# Main_CPU.net
KiCad netlist of a schematic drawn in Altium Designer
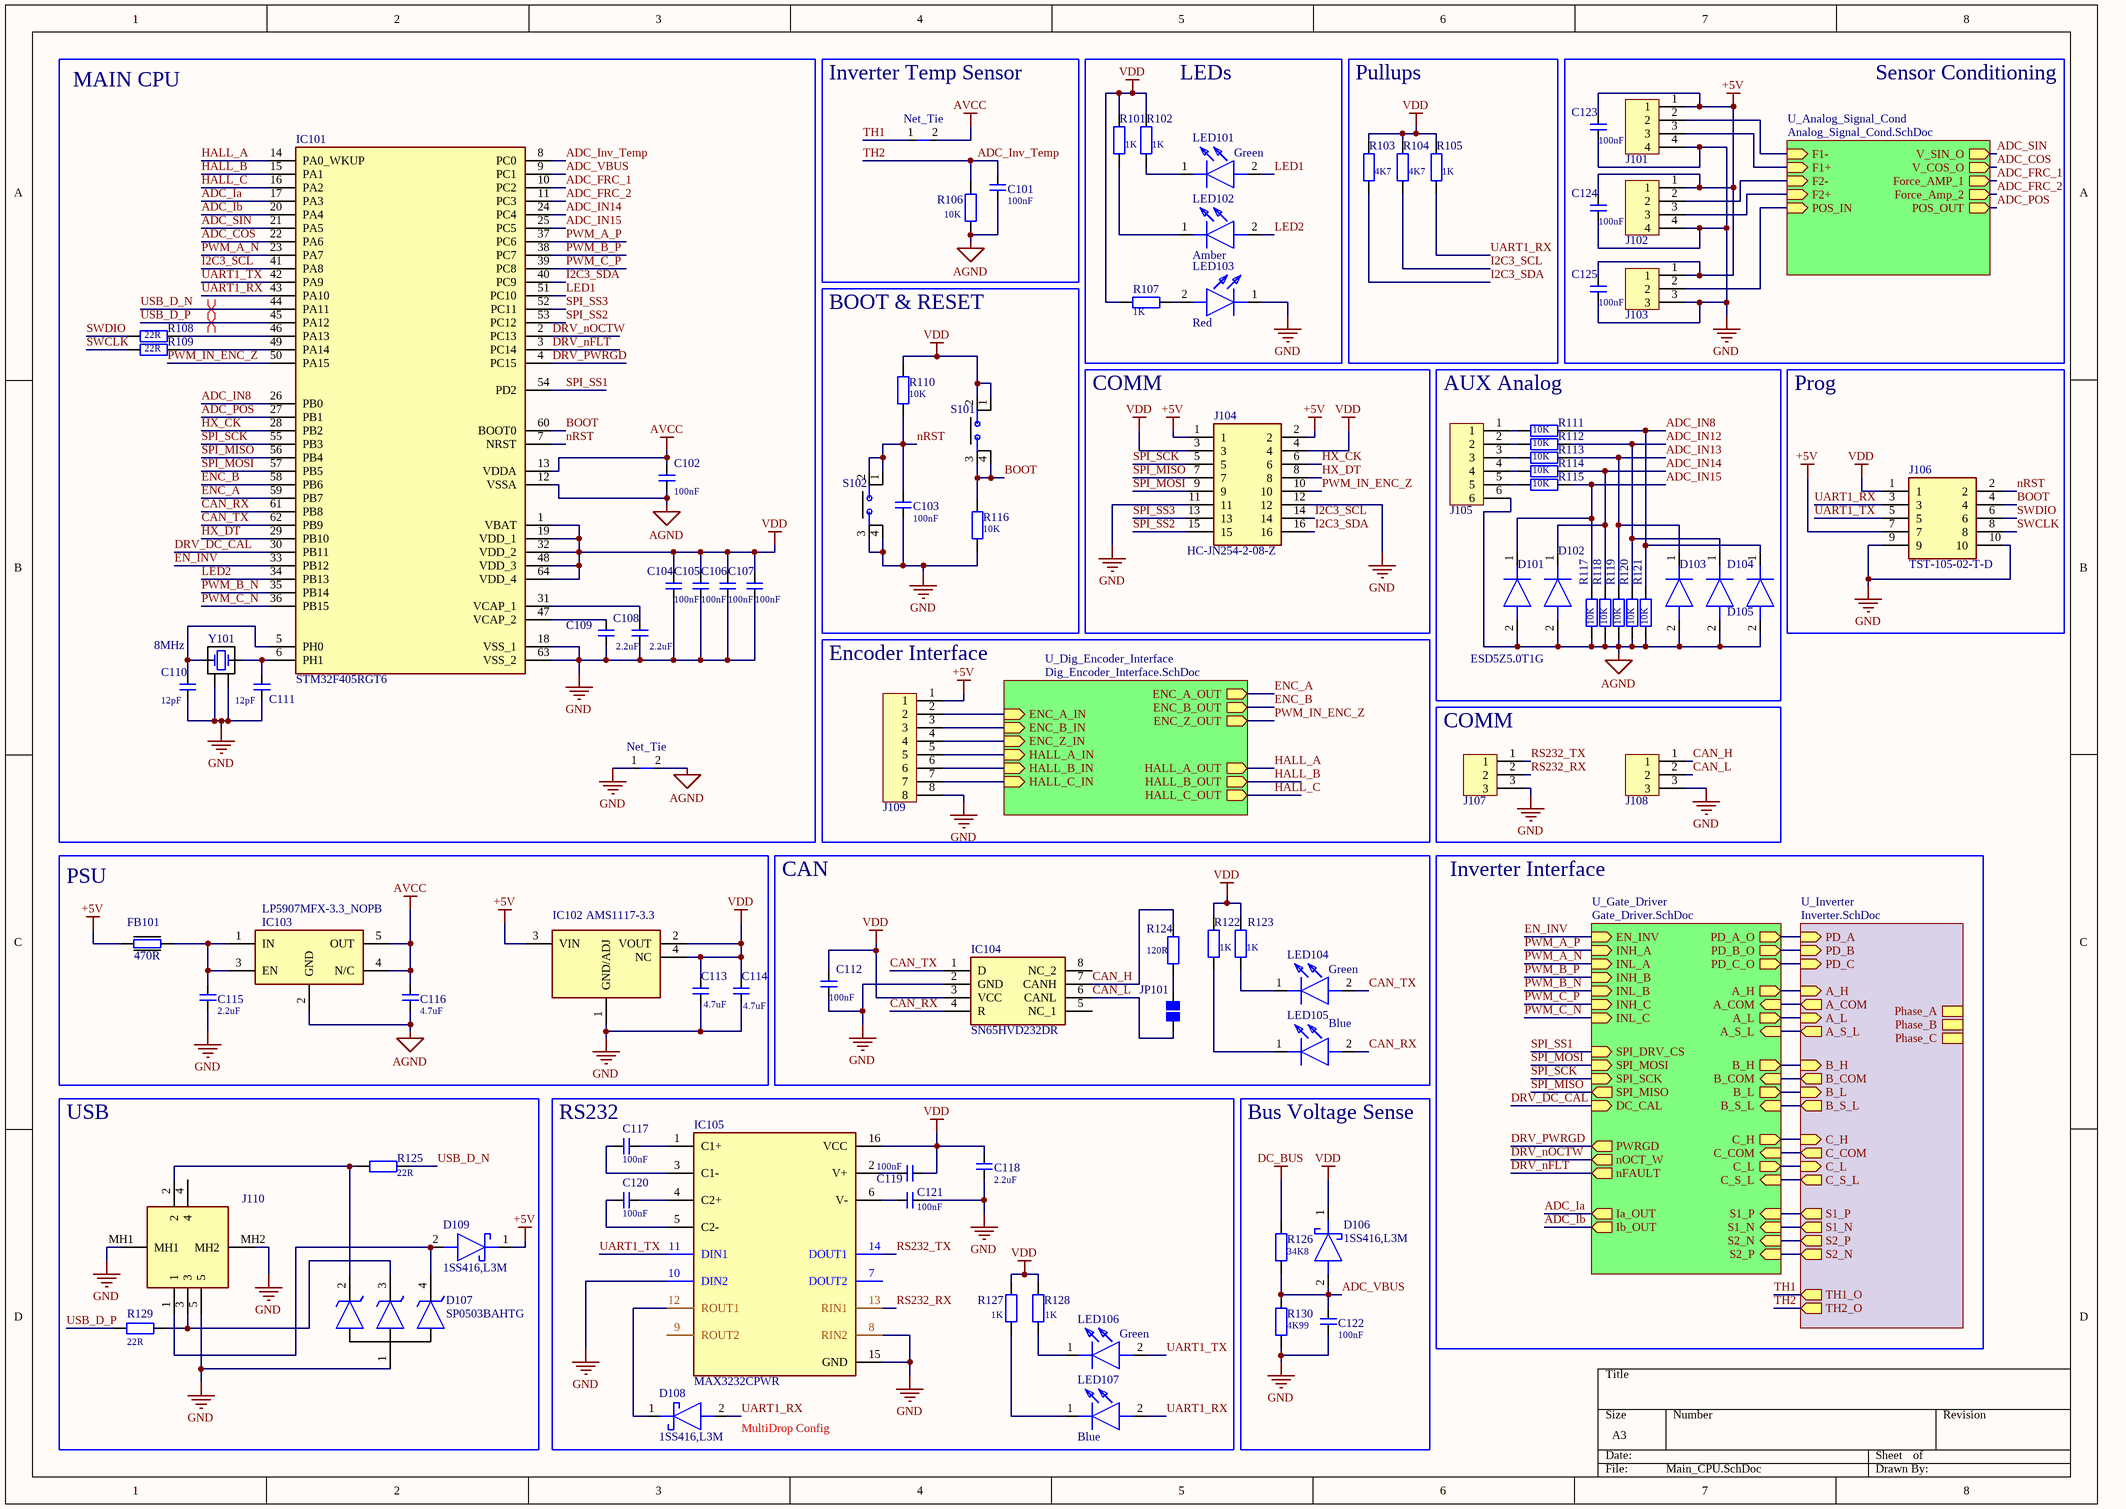
[diagram p0: Main_CPU.SchDoc]

(export (version "E")
  (design (tool "Eeschema 10.0.6"))
  (components
    (comp (ref "C101")
      (value "100nF")
      (footprint "CAPC1005X06N")
      (description "Capacitor")
      (fields (field (name "MPN") "GCM155R71H104KE02D") (field (name "Comment") "Cap"))
      (libsource (lib "SamacSys") (part "Cap"))
    )
    (comp (ref "C102")
      (value "100nF")
      (footprint "CAPC1005X06N")
      (description "Capacitor")
      (fields (field (name "MPN") "GCM155R71H104KE02D") (field (name "Comment") "Cap"))
      (libsource (lib "SamacSys") (part "Cap"))
    )
    (comp (ref "C103")
      (value "100nF")
      (footprint "CAPC1005X06N")
      (description "Capacitor")
      (fields (field (name "MPN") "GCM155R71H104KE02D") (field (name "Comment") "Cap"))
      (libsource (lib "SamacSys") (part "Cap"))
    )
    (comp (ref "C104")
      (value "100nF")
      (footprint "CAPC1005X06N")
      (description "Capacitor")
      (fields (field (name "MPN") "GCM155R71H104KE02D") (field (name "Comment") "Cap"))
      (libsource (lib "SamacSys") (part "Cap"))
    )
    (comp (ref "C105")
      (value "100nF")
      (footprint "CAPC1005X06N")
      (description "Capacitor")
      (fields (field (name "MPN") "GCM155R71H104KE02D") (field (name "Comment") "Cap"))
      (libsource (lib "SamacSys") (part "Cap"))
    )
    (comp (ref "C106")
      (value "100nF")
      (footprint "CAPC1005X06N")
      (description "Capacitor")
      (fields (field (name "MPN") "GCM155R71H104KE02D") (field (name "Comment") "Cap"))
      (libsource (lib "SamacSys") (part "Cap"))
    )
    (comp (ref "C107")
      (value "100nF")
      (footprint "CAPC1005X06N")
      (description "Capacitor")
      (fields (field (name "MPN") "GCM155R71H104KE02D") (field (name "Comment") "Cap"))
      (libsource (lib "SamacSys") (part "Cap"))
    )
    (comp (ref "C108")
      (value "2.2uF")
      (footprint "CAPC1005X06N")
      (description "Capacitor")
      (fields (field (name "MPN") "GRM155Z71A225KE44D") (field (name "Comment") "Cap"))
      (libsource (lib "SamacSys") (part "Cap"))
    )
    (comp (ref "C109")
      (value "2.2uF")
      (footprint "CAPC1005X06N")
      (description "Capacitor")
      (fields (field (name "MPN") "GRM155Z71A225KE44D") (field (name "Comment") "Cap"))
      (libsource (lib "SamacSys") (part "Cap"))
    )
    (comp (ref "C110")
      (value "12pF")
      (footprint "CAPC1005X06N")
      (description "Capacitor")
      (fields (field (name "MPN") "GRM1555C1H120JA01D") (field (name "Comment") "Cap"))
      (libsource (lib "SamacSys") (part "Cap"))
    )
    (comp (ref "C111")
      (value "12pF")
      (footprint "CAPC1005X06N")
      (description "Capacitor")
      (fields (field (name "MPN") "GRM1555C1H120JA01D") (field (name "Comment") "Cap"))
      (libsource (lib "SamacSys") (part "Cap"))
    )
    (comp (ref "C112")
      (value "100nF")
      (footprint "CAPC1005X06N")
      (description "Capacitor")
      (fields (field (name "MPN") "GCM155R71H104KE02D") (field (name "Comment") "Cap"))
      (libsource (lib "SamacSys") (part "Cap"))
    )
    (comp (ref "C113")
      (value "4.7uF")
      (footprint "CAPC3225X17N")
      (description "Capacitor")
      (fields (field (name "MPN") "CC1210KKX7R8BB475") (field (name "Comment") "Cap"))
      (libsource (lib "SamacSys") (part "Cap"))
    )
    (comp (ref "C114")
      (value "4.7uF")
      (footprint "CAPC3225X17N")
      (description "Capacitor")
      (fields (field (name "MPN") "CC1210KKX7R8BB475") (field (name "Comment") "Cap"))
      (libsource (lib "SamacSys") (part "Cap"))
    )
    (comp (ref "C115")
      (value "2.2uF")
      (footprint "CAPC1005X06N")
      (description "Capacitor")
      (fields (field (name "MPN") "GRM155Z71A225KE44D") (field (name "Comment") "Cap"))
      (libsource (lib "SamacSys") (part "Cap"))
    )
    (comp (ref "C116")
      (value "4.7uF")
      (footprint "CAPC3225X17N")
      (description "Capacitor")
      (fields (field (name "MPN") "CC1210KKX7R8BB475") (field (name "Comment") "Cap"))
      (libsource (lib "SamacSys") (part "Cap"))
    )
    (comp (ref "C117")
      (value "100nF")
      (footprint "CAPC1005X06N")
      (description "Capacitor")
      (fields (field (name "MPN") "GCM155R71H104KE02D") (field (name "Comment") "Cap"))
      (libsource (lib "SamacSys") (part "Cap"))
    )
    (comp (ref "C118")
      (value "2.2uF")
      (footprint "CAPC1005X06N")
      (description "Capacitor")
      (fields (field (name "MPN") "GRM155Z71A225KE44D") (field (name "Comment") "Cap"))
      (libsource (lib "SamacSys") (part "Cap"))
    )
    (comp (ref "C119")
      (value "100nF")
      (footprint "CAPC1005X06N")
      (description "Capacitor")
      (fields (field (name "MPN") "GCM155R71H104KE02D") (field (name "Comment") "Cap"))
      (libsource (lib "SamacSys") (part "Cap"))
    )
    (comp (ref "C120")
      (value "100nF")
      (footprint "CAPC1005X06N")
      (description "Capacitor")
      (fields (field (name "MPN") "GCM155R71H104KE02D") (field (name "Comment") "Cap"))
      (libsource (lib "SamacSys") (part "Cap"))
    )
    (comp (ref "C121")
      (value "100nF")
      (footprint "CAPC1005X06N")
      (description "Capacitor")
      (fields (field (name "MPN") "GCM155R71H104KE02D") (field (name "Comment") "Cap"))
      (libsource (lib "SamacSys") (part "Cap"))
    )
    (comp (ref "C122")
      (value "100nF")
      (footprint "CAPC1005X06N")
      (description "Capacitor")
      (fields (field (name "MPN") "GCM155R71H104KE02D") (field (name "Comment") "Cap"))
      (libsource (lib "SamacSys") (part "Cap"))
    )
    (comp (ref "C123")
      (value "100nF")
      (footprint "CAPC1005X06N")
      (description "Capacitor")
      (fields (field (name "MPN") "GCM155R71H104KE02D") (field (name "Comment") "Cap"))
      (libsource (lib "SamacSys") (part "Cap"))
    )
    (comp (ref "C124")
      (value "100nF")
      (footprint "CAPC1005X06N")
      (description "Capacitor")
      (fields (field (name "MPN") "GCM155R71H104KE02D") (field (name "Comment") "Cap"))
      (libsource (lib "SamacSys") (part "Cap"))
    )
    (comp (ref "C125")
      (value "100nF")
      (footprint "CAPC1005X06N")
      (description "Capacitor")
      (fields (field (name "MPN") "GCM155R71H104KE02D") (field (name "Comment") "Cap"))
      (libsource (lib "SamacSys") (part "Cap"))
    )
    (comp (ref "D101")
      (value "ESD5Z5.0T1G")
      (footprint "SamacSys:SODFL1608X70N")
      (description "Diode")
      (fields (field (name "MOUSER PART NUMBER") "863-ESD5Z5.0T1G"))
      (libsource (lib "SamacSys") (part "ESD5Z5.0T1G"))
    )
    (comp (ref "D102")
      (value "ESD5Z5.0T1G")
      (footprint "SamacSys:SODFL1608X70N")
      (description "Diode")
      (fields (field (name "MPN") "863-ESD5Z5.0T1G"))
      (libsource (lib "SamacSys") (part "ESD5Z5.0T1G"))
    )
    (comp (ref "D103")
      (value "ESD5Z5.0T1G")
      (footprint "SamacSys:SODFL1608X70N")
      (description "Diode")
      (fields (field (name "MPN") "863-ESD5Z5.0T1G"))
      (libsource (lib "SamacSys") (part "ESD5Z5.0T1G"))
    )
    (comp (ref "D104")
      (value "ESD5Z5.0T1G")
      (footprint "SamacSys:SODFL1608X70N")
      (description "Diode")
      (fields (field (name "MPN") "863-ESD5Z5.0T1G"))
      (libsource (lib "SamacSys") (part "ESD5Z5.0T1G"))
    )
    (comp (ref "D105")
      (value "ESD5Z5.0T1G")
      (footprint "SamacSys:SODFL1608X70N")
      (description "Diode")
      (fields (field (name "MOUSER PART NUMBER") "863-ESD5Z5.0T1G"))
      (libsource (lib "SamacSys") (part "ESD5Z5.0T1G"))
    )
    (comp (ref "D106")
      (value "1SS416,L3M")
      (footprint "SamacSys:SODFL1006X45N")
      (description "Schottky Diode")
      (fields (field (name "MPN") "1SS416,L3M(B") (field (name "MOUSER PART NUMBER") "757-1SS416L3M"))
      (libsource (lib "SamacSys") (part "1SS416,L3M"))
    )
    (comp (ref "D107")
      (value "SP0503BAHTG")
      (footprint "SP0503BAHTG")
      (description "TVS Diode (Uni-directional)")
      (fields (field (name "MOUSER PART NUMBER") "576-SP0503BAHTG"))
      (libsource (lib "SamacSys") (part "SP0503BAHTG"))
    )
    (comp (ref "D108")
      (value "1SS416,L3M")
      (footprint "SamacSys:SODFL1006X45N")
      (description "Schottky Diode")
      (fields (field (name "MPN") "1SS416,L3M(B") (field (name "MOUSER PART NUMBER") "757-1SS416L3M"))
      (libsource (lib "SamacSys") (part "1SS416,L3M"))
    )
    (comp (ref "D109")
      (value "1SS416,L3M")
      (footprint "SODFL1006X45N")
      (description "Schottky Diode")
      (fields (field (name "MPN") "1SS416,L3M(B") (field (name "MOUSER PART NUMBER") "757-1SS416L3M"))
      (libsource (lib "SamacSys") (part "1SS416,L3M"))
    )
    (comp (ref "FB101")
      (value "470R")
      (footprint "SamacSys:BLM18SP221SN1B")
      (description "Ferrite Bead")
      (fields (field (name "MPN") "BLM18KG471SN1D") (field (name "MOUSER PART NUMBER") "81-BLM18KG471SN1D"))
      (libsource (lib "SamacSys") (part "BLM18KG471SN1D"))
    )
    (comp (ref "IC101")
      (value "STM32F405RGT6")
      (footprint "SamacSys:QFP50P1200X1200X160-64N")
      (description "Integrated Circuit")
      (fields (field (name "MOUSER PART NUMBER") "511-STM32F405RGT6"))
      (libsource (lib "SamacSys") (part "STM32F405RGT6"))
    )
    (comp (ref "IC102")
      (value "AMS1117-3.3")
      (footprint "SamacSys:SOT229P700X180-4N")
      (description "Integrated Circuit")
      (libsource (lib "SamacSys") (part "AMS1117-3.3"))
    )
    (comp (ref "IC103")
      (value "LP5907MFX-3.3_NOPB")
      (footprint "SamacSys:SOT95P280X145-5N")
      (description "Integrated Circuit")
      (fields
        (field (name "MPN") "LP5907MFX-3.3/NOPB")
        (field (name "MOUSER PART NUMBER") "595-LP5907MFX-3.3NPB")
      )
      (libsource (lib "SamacSys") (part "LP5907MFX-3.3_NOPB"))
    )
    (comp (ref "IC104")
      (value "SN65HVD232DR")
      (footprint "SamacSys:SOIC127P600X175-8N")
      (description "Integrated Circuit")
      (libsource (lib "*") (part "SN65HVD232DR"))
    )
    (comp (ref "IC105")
      (value "MAX3232CPWR")
      (footprint "SamacSys:SOP65P640X120-16N")
      (description "Integrated Circuit")
      (libsource (lib "SamacSys") (part "MAX3232CPWR"))
    )
    (comp (ref "J101")
      (value "XH2_54_4p")
      (footprint "XH2.54-4P")
      (fields (field (name "MPN") "BX-XH2.54-4PZZ"))
      (libsource (lib "SamacSys") (part "XH2_54_4p"))
    )
    (comp (ref "J102")
      (value "XH2_54_4p")
      (footprint "XH2.54-4P")
      (fields (field (name "MPN") "BX-XH2.54-4PZZ"))
      (libsource (lib "SamacSys") (part "XH2_54_4p"))
    )
    (comp (ref "J103")
      (value "XH2_54_3p")
      (footprint "XH2.54-3P")
      (fields (field (name "MPN") "ZX-XH2.54-3PZZ"))
      (libsource (lib "SamacSys") (part "XH2_54_3p"))
    )
    (comp (ref "J104")
      (value "TST-108-02-T-D")
      (footprint "SamacSys:SHDR16W64P254_2X8_2794X927X940P")
      (description "Connector")
      (fields (field (name "MOUSER PART NUMBER") "200-TST10802TD") (field (name "MPN") "HC-JN254-2-08-Z"))
      (libsource (lib "SamacSys") (part "TST-108-02-T-D"))
    )
    (comp (ref "J105")
      (value "PCB_Conn_6P")
      (footprint "PCB_CONN_6")
      (libsource (lib "SamacSys") (part "PCB_Conn_6P"))
    )
    (comp (ref "J106")
      (value "TST-105-02-T-D")
      (footprint "TST-105-XX-Y-D")
      (description "Connector")
      (fields (field (name "MPN") "ZX-IDC2.54-2-5PZZ") (field (name "MOUSER PART NUMBER") "200-TST10502TD"))
      (libsource (lib "SamacSys") (part "TST-105-02-T-D"))
    )
    (comp (ref "J107")
      (value "XH2_54_3p")
      (footprint "XH2.54-3P")
      (fields (field (name "MPN") "ZX-XH2.54-3PZZ"))
      (libsource (lib "SamacSys") (part "XH2_54_3p"))
    )
    (comp (ref "J108")
      (value "XH2_54_3p")
      (footprint "XH2.54-3P")
      (fields (field (name "MPN") "ZX-XH2.54-3PZZ"))
      (libsource (lib "SamacSys") (part "XH2_54_3p"))
    )
    (comp (ref "J109")
      (value "PCB_Conn_8p")
      (footprint "PCB_CONN_8")
      (libsource (lib "SamacSys") (part "PCB_Conn_8p"))
    )
    (comp (ref "J110")
      (value "10119313-301TLF")
      (footprint "10119313301TLF")
      (description "Connector")
      (fields (field (name "MPN") "HX MINI5P T") (field (name "MOUSER PART NUMBER") "649-10119313-301TLF"))
      (libsource (lib "SamacSys") (part "10119313-301TLF"))
    )
    (comp (ref "JP101") (value "Jumper") (footprint "Jumper") (libsource (lib "SamacSys") (part "Jumper")))
    (comp (ref "LED101")
      (value "Green")
      (footprint "SamacSys:LEDC1608X80N")
      (description "LED")
      (fields (field (name "MPN") "XL-1608UGC-04") (field (name "MOUSER PART NUMBER") "710-150060SS75000"))
      (libsource (lib "*") (part "150060SS75000"))
    )
    (comp (ref "LED102")
      (value "Amber")
      (footprint "SamacSys:LEDC1608X80N")
      (description "LED")
      (fields
        (field (name "MPN") "19-217UYOC/S3112/TR8")
        (field (name "MOUSER PART NUMBER") "710-150060SS75000")
      )
      (libsource (lib "*") (part "150060SS75000"))
    )
    (comp (ref "LED103")
      (value "Red")
      (footprint "SamacSys:LEDC1608X80N")
      (description "LED")
      (fields (field (name "MPN") "XL-1608SURC-06") (field (name "MOUSER PART NUMBER") "710-150060SS75000"))
      (libsource (lib "*") (part "150060SS75000"))
    )
    (comp (ref "LED104")
      (value "Green")
      (footprint "SamacSys:LEDC1608X80N")
      (description "LED")
      (fields (field (name "MPN") "XL-1608UGC-04") (field (name "MOUSER PART NUMBER") "710-150060SS75000"))
      (libsource (lib "*") (part "150060SS75000"))
    )
    (comp (ref "LED105")
      (value "Blue")
      (footprint "SamacSys:LEDC1608X80N")
      (description "LED")
      (fields (field (name "MPN") "XL-1608UBC-04") (field (name "MOUSER PART NUMBER") "710-150060SS75000"))
      (libsource (lib "*") (part "150060SS75000"))
    )
    (comp (ref "LED106")
      (value "Green")
      (footprint "LEDC1608X80N")
      (description "LED")
      (fields (field (name "MPN") "XL-1608UGC-04") (field (name "MOUSER PART NUMBER") "710-150060SS75000"))
      (libsource (lib "*") (part "150060SS75000"))
    )
    (comp (ref "LED107")
      (value "Blue")
      (footprint "LEDC1608X80N")
      (description "LED")
      (fields (field (name "MPN") "XL-1608UBC-04") (field (name "MOUSER PART NUMBER") "710-150060SS75000"))
      (libsource (lib "*") (part "150060SS75000"))
    )
    (comp (ref "NT101")
      (value "Net_Tie")
      (footprint "Net_Tie_SMD")
      (description "Net Tie")
      (libsource (lib "SamacSys") (part "Net_Tie"))
    )
    (comp (ref "NT102")
      (value "Net_Tie")
      (footprint "Net_Tie_SMD")
      (description "Net Tie")
      (libsource (lib "SamacSys") (part "Net_Tie"))
    )
    (comp (ref "R101")
      (value "1K")
      (footprint "RESC1005X04N")
      (description "Resistor")
      (fields (field (name "MPN") "RC0402FR-071KL") (field (name "Comment") "R"))
      (libsource (lib "SamacSys") (part "R"))
    )
    (comp (ref "R102")
      (value "1K")
      (footprint "RESC1005X04N")
      (description "Resistor")
      (fields (field (name "MPN") "RC0402FR-071KL") (field (name "Comment") "R"))
      (libsource (lib "SamacSys") (part "R"))
    )
    (comp (ref "R103")
      (value "4K7")
      (footprint "RESC1005X04N")
      (description "Resistor")
      (fields (field (name "MPN") "RC0402FR-074K7L") (field (name "Comment") "R"))
      (libsource (lib "SamacSys") (part "R"))
    )
    (comp (ref "R104")
      (value "4K7")
      (footprint "RESC1005X04N")
      (description "Resistor")
      (fields (field (name "MPN") "RC0402FR-074K7L") (field (name "Comment") "R"))
      (libsource (lib "SamacSys") (part "R"))
    )
    (comp (ref "R105")
      (value "1K")
      (footprint "RESC1005X04N")
      (description "Resistor")
      (fields (field (name "MPN") "RC0402FR-071KL") (field (name "Comment") "R"))
      (libsource (lib "SamacSys") (part "R"))
    )
    (comp (ref "R106")
      (value "10K")
      (footprint "RESC1005X04N")
      (description "Resistor")
      (fields (field (name "MPN") "RC0402FR-0710KL") (field (name "Comment") "R"))
      (libsource (lib "") (part "R_1"))
    )
    (comp (ref "R107")
      (value "1K")
      (footprint "RESC1005X04N")
      (description "Resistor")
      (fields (field (name "MPN") "RC0402FR-071KL") (field (name "Comment") "R"))
      (libsource (lib "") (part "R_2"))
    )
    (comp (ref "R108")
      (value "22R")
      (footprint "RESC1005X04N")
      (description "Resistor")
      (fields (field (name "MPN") "RC0402FR-0722RL") (field (name "Comment") "R"))
      (libsource (lib "") (part "R_2"))
    )
    (comp (ref "R109")
      (value "22R")
      (footprint "RESC1005X04N")
      (description "Resistor")
      (fields (field (name "MPN") "RC0402FR-0722RL") (field (name "Comment") "R"))
      (libsource (lib "") (part "R_2"))
    )
    (comp (ref "R110")
      (value "10K")
      (footprint "RESC1005X04N")
      (description "Resistor")
      (fields (field (name "MPN") "RC0402FR-0710KL") (field (name "Comment") "R"))
      (libsource (lib "") (part "R_1"))
    )
    (comp (ref "R111")
      (value "10K")
      (footprint "RESC1005X04N")
      (description "Resistor")
      (fields (field (name "MPN") "RC0402FR-0710KL") (field (name "Comment") "R"))
      (libsource (lib "") (part "R_2"))
    )
    (comp (ref "R112")
      (value "10K")
      (footprint "RESC1005X04N")
      (description "Resistor")
      (fields (field (name "MPN") "RC0402FR-0710KL") (field (name "Comment") "R"))
      (libsource (lib "") (part "R_2"))
    )
    (comp (ref "R113")
      (value "10K")
      (footprint "RESC1005X04N")
      (description "Resistor")
      (fields (field (name "MPN") "RC0402FR-0710KL") (field (name "Comment") "R"))
      (libsource (lib "") (part "R_2"))
    )
    (comp (ref "R114")
      (value "10K")
      (footprint "RESC1005X04N")
      (description "Resistor")
      (fields (field (name "MPN") "RC0402FR-0710KL") (field (name "Comment") "R"))
      (libsource (lib "") (part "R_2"))
    )
    (comp (ref "R115")
      (value "10K")
      (footprint "RESC1005X04N")
      (description "Resistor")
      (fields (field (name "MPN") "RC0402FR-0710KL") (field (name "Comment") "R"))
      (libsource (lib "") (part "R_2"))
    )
    (comp (ref "R116")
      (value "10K")
      (footprint "RESC1005X04N")
      (description "Resistor")
      (fields (field (name "MPN") "RC0402FR-0710KL") (field (name "Comment") "R"))
      (libsource (lib "") (part "R_1"))
    )
    (comp (ref "R117")
      (value "10K")
      (footprint "RESC1005X04N")
      (description "Resistor")
      (fields (field (name "MPN") "RC0402FR-0710KL") (field (name "Comment") "R"))
      (libsource (lib "SamacSys") (part "R"))
    )
    (comp (ref "R118")
      (value "10K")
      (footprint "RESC1005X04N")
      (description "Resistor")
      (fields (field (name "MPN") "RC0402FR-0710KL") (field (name "Comment") "R"))
      (libsource (lib "SamacSys") (part "R"))
    )
    (comp (ref "R119")
      (value "10K")
      (footprint "RESC1005X04N")
      (description "Resistor")
      (fields (field (name "MPN") "RC0402FR-0710KL") (field (name "Comment") "R"))
      (libsource (lib "SamacSys") (part "R"))
    )
    (comp (ref "R120")
      (value "10K")
      (footprint "RESC1005X04N")
      (description "Resistor")
      (fields (field (name "MPN") "RC0402FR-0710KL") (field (name "Comment") "R"))
      (libsource (lib "SamacSys") (part "R"))
    )
    (comp (ref "R121")
      (value "10K")
      (footprint "RESC1005X04N")
      (description "Resistor")
      (fields (field (name "MPN") "RC0402FR-0710KL") (field (name "Comment") "R"))
      (libsource (lib "SamacSys") (part "R"))
    )
    (comp (ref "R122")
      (value "1K")
      (footprint "RESC1005X04N")
      (description "Resistor")
      (fields (field (name "MPN") "RC0402FR-071KL") (field (name "Comment") "R"))
      (libsource (lib "") (part "R_1"))
    )
    (comp (ref "R123")
      (value "1K")
      (footprint "RESC1005X04N")
      (description "Resistor")
      (fields (field (name "MPN") "RC0402FR-071KL") (field (name "Comment") "R"))
      (libsource (lib "") (part "R_1"))
    )
    (comp (ref "R124")
      (value "120R")
      (footprint "RESC3216X06N")
      (description "Resistor")
      (fields (field (name "MPN") "RC1206FR-07120RL") (field (name "Comment") "R"))
      (libsource (lib "") (part "R_1"))
    )
    (comp (ref "R125")
      (value "22R")
      (footprint "RESC1005X04N")
      (description "Resistor")
      (fields (field (name "MPN") "RC0402FR-0722RL") (field (name "Comment") "R"))
      (libsource (lib "") (part "R_2"))
    )
    (comp (ref "R126")
      (value "34K8")
      (footprint "RESC1005X04N")
      (description "Resistor")
      (fields (field (name "MPN") "RC0402FR-0734K8L") (field (name "Comment") "R"))
      (libsource (lib "SamacSys") (part "R"))
    )
    (comp (ref "R127")
      (value "1K")
      (footprint "RESC1005X04N")
      (description "Resistor")
      (fields (field (name "MPN") "RC0402FR-071KL") (field (name "Comment") "R"))
      (libsource (lib "") (part "R_1"))
    )
    (comp (ref "R128")
      (value "1K")
      (footprint "RESC1005X04N")
      (description "Resistor")
      (fields (field (name "MPN") "RC0402FR-071KL") (field (name "Comment") "R"))
      (libsource (lib "") (part "R_1"))
    )
    (comp (ref "R129")
      (value "22R")
      (footprint "RESC1005X04N")
      (description "Resistor")
      (fields (field (name "MPN") "RC0402FR-0722RL") (field (name "Comment") "R"))
      (libsource (lib "") (part "R_2"))
    )
    (comp (ref "R130")
      (value "4K99")
      (footprint "RESC1005X04N")
      (description "Resistor")
      (fields (field (name "MPN") "RC0402FR-074K99L") (field (name "Comment") "R"))
      (libsource (lib "SamacSys") (part "R"))
    )
    (comp (ref "S101")
      (value "TS18-5-25-SL-260-SMT-TR")
      (footprint "SamacSys:TS18525SL260SMTTR")
      (description "Switch")
      (fields
        (field (name "MPN") "GT-TC084B-H015-L5")
        (field (name "MOUSER PART NUMBER") "179-TS18525SL260SMTT")
      )
      (libsource (lib "SamacSys") (part "TS18-5-25-SL-260-SMT-TR"))
    )
    (comp (ref "S102")
      (value "TS18-5-25-SL-260-SMT-TR")
      (footprint "SamacSys:TS18525SL260SMTTR")
      (description "Switch")
      (fields
        (field (name "MPN") "GT-TC084B-H015-L5")
        (field (name "MOUSER PART NUMBER") "179-TS18525SL260SMTT")
      )
      (libsource (lib "SamacSys") (part "TS18-5-25-SL-260-SMT-TR"))
    )
    (comp (ref "Y101")
      (value "8MHz")
      (footprint "SamacSys:830105863709")
      (description "Crystal or Oscillator")
      (fields
        (field (name "MPN") "XL2EL89COI-111YLC-8M")
        (field (name "MOUSER PART NUMBER") "710-830105863709")
      )
      (libsource (lib "SamacSys") (part "XTAL_3225"))
    )
  )
  (nets
    (net (code "1") (name "+5V") (class "Default")
      (node (ref "C123") (pin "2") (pinfunction "2_2") (pintype "passive"))
      (node (ref "C124") (pin "2") (pinfunction "2_2") (pintype "passive"))
      (node (ref "C125") (pin "2") (pinfunction "2_2") (pintype "passive"))
      (node (ref "D109") (pin "1") (pinfunction "K_1") (pintype "passive"))
      (node (ref "FB101") (pin "1") (pinfunction "1_1") (pintype "passive"))
      (node (ref "IC102") (pin "3") (pinfunction "VIN_3") (pintype "passive"))
      (node (ref "J101") (pin "1") (pinfunction "1_1") (pintype "passive"))
      (node (ref "J102") (pin "1") (pinfunction "1_1") (pintype "passive"))
      (node (ref "J103") (pin "1") (pinfunction "1_1") (pintype "passive"))
      (node (ref "J104") (pin "1") (pinfunction "1_1") (pintype "passive"))
      (node (ref "J104") (pin "2") (pinfunction "2_2") (pintype "passive"))
      (node (ref "J106") (pin "7") (pinfunction "7_7") (pintype "passive"))
      (node (ref "J109") (pin "1") (pinfunction "1_1") (pintype "passive"))
    )
    (net (code "2") (name "/ADC_COS") (class "Default")
      (node (ref "IC101") (pin "22") (pinfunction "PA6_22") (pintype "passive"))
    )
    (net (code "3") (name "/ADC_FRC_1") (class "Default")
      (node (ref "IC101") (pin "10") (pinfunction "PC2_10") (pintype "passive"))
    )
    (net (code "4") (name "/ADC_FRC_2") (class "Default")
      (node (ref "IC101") (pin "11") (pinfunction "PC3_11") (pintype "passive"))
    )
    (net (code "5") (name "/ADC_IN8") (class "Default")
      (node (ref "D105") (pin "1") (pinfunction "K_1") (pintype "passive"))
      (node (ref "IC101") (pin "26") (pinfunction "PB0_26") (pintype "passive"))
      (node (ref "R111") (pin "1") (pinfunction "1_1") (pintype "passive"))
      (node (ref "R121") (pin "1") (pinfunction "1_1") (pintype "passive"))
    )
    (net (code "6") (name "/ADC_IN12") (class "Default")
      (node (ref "D104") (pin "1") (pinfunction "K_1") (pintype "passive"))
      (node (ref "R112") (pin "1") (pinfunction "1_1") (pintype "passive"))
      (node (ref "R120") (pin "1") (pinfunction "1_1") (pintype "passive"))
    )
    (net (code "7") (name "/ADC_IN13") (class "Default")
      (node (ref "D103") (pin "1") (pinfunction "K_1") (pintype "passive"))
      (node (ref "R113") (pin "1") (pinfunction "1_1") (pintype "passive"))
      (node (ref "R119") (pin "1") (pinfunction "1_1") (pintype "passive"))
    )
    (net (code "8") (name "/ADC_IN14") (class "Default")
      (node (ref "D102") (pin "1") (pinfunction "K_1") (pintype "passive"))
      (node (ref "IC101") (pin "24") (pinfunction "PC4_24") (pintype "passive"))
      (node (ref "R114") (pin "1") (pinfunction "1_1") (pintype "passive"))
      (node (ref "R118") (pin "1") (pinfunction "1_1") (pintype "passive"))
    )
    (net (code "9") (name "/ADC_IN15") (class "Default")
      (node (ref "D101") (pin "1") (pinfunction "K_1") (pintype "passive"))
      (node (ref "IC101") (pin "25") (pinfunction "PC5_25") (pintype "passive"))
      (node (ref "R115") (pin "1") (pinfunction "1_1") (pintype "passive"))
      (node (ref "R117") (pin "1") (pinfunction "1_1") (pintype "passive"))
    )
    (net (code "10") (name "/ADC_Ia") (class "Default")
      (node (ref "IC101") (pin "17") (pinfunction "PA3_17") (pintype "passive"))
    )
    (net (code "11") (name "/ADC_Ib") (class "Default")
      (node (ref "IC101") (pin "20") (pinfunction "PA4_20") (pintype "passive"))
    )
    (net (code "12") (name "/ADC_Inv_Temp") (class "Default")
      (node (ref "C101") (pin "2") (pinfunction "2_2") (pintype "passive"))
      (node (ref "IC101") (pin "8") (pinfunction "PC0_8") (pintype "passive"))
      (node (ref "R106") (pin "2") (pinfunction "2_2") (pintype "passive"))
    )
    (net (code "13") (name "/ADC_POS") (class "Default")
      (node (ref "IC101") (pin "27") (pinfunction "PB1_27") (pintype "passive"))
    )
    (net (code "14") (name "/ADC_SIN") (class "Default")
      (node (ref "IC101") (pin "21") (pinfunction "PA5_21") (pintype "passive"))
    )
    (net (code "15") (name "/ADC_VBUS") (class "Default")
      (node (ref "C122") (pin "2") (pinfunction "2_2") (pintype "passive"))
      (node (ref "D106") (pin "2") (pinfunction "A_2") (pintype "passive"))
      (node (ref "IC101") (pin "9") (pinfunction "PC1_9") (pintype "passive"))
      (node (ref "R126") (pin "2") (pinfunction "2_2") (pintype "passive"))
      (node (ref "R130") (pin "1") (pinfunction "1_1") (pintype "passive"))
    )
    (net (code "20") (name "/BOOT") (class "Default")
      (node (ref "IC101") (pin "60") (pinfunction "BOOT0_60") (pintype "passive"))
      (node (ref "J106") (pin "4") (pinfunction "4_4") (pintype "passive"))
      (node (ref "R116") (pin "2") (pinfunction "2_2") (pintype "passive"))
      (node (ref "S101") (pin "3") (pinfunction "COM_1_3") (pintype "passive"))
      (node (ref "S101") (pin "4") (pinfunction "COM_2_4") (pintype "passive"))
    )
    (net (code "25") (name "/CAN_H") (class "Default")
      (node (ref "IC104") (pin "7") (pinfunction "CANH_7") (pintype "passive"))
      (node (ref "J108") (pin "1") (pinfunction "1_1") (pintype "passive"))
      (node (ref "R124") (pin "2") (pinfunction "2_2") (pintype "passive"))
    )
    (net (code "26") (name "/CAN_L") (class "Default")
      (node (ref "IC104") (pin "6") (pinfunction "CANL_6") (pintype "passive"))
      (node (ref "J108") (pin "2") (pinfunction "2_2") (pintype "passive"))
      (node (ref "JP101") (pin "1") (pintype "passive"))
    )
    (net (code "27") (name "/CAN_RX") (class "Default")
      (node (ref "IC101") (pin "61") (pinfunction "PB8_61") (pintype "passive"))
      (node (ref "IC104") (pin "4") (pinfunction "R_4") (pintype "passive"))
      (node (ref "LED105") (pin "2") (pinfunction "A_2") (pintype "passive"))
    )
    (net (code "28") (name "/CAN_TX") (class "Default")
      (node (ref "IC101") (pin "62") (pinfunction "PB9_62") (pintype "passive"))
      (node (ref "IC104") (pin "1") (pinfunction "D_1") (pintype "passive"))
      (node (ref "LED104") (pin "2") (pinfunction "A_2") (pintype "passive"))
    )
    (net (code "33") (name "/DRV_DC_CAL") (class "Default")
      (node (ref "IC101") (pin "30") (pinfunction "PB11_30") (pintype "passive"))
    )
    (net (code "34") (name "/DRV_PWRGD") (class "Default")
      (node (ref "IC101") (pin "4") (pinfunction "PC15_4") (pintype "passive"))
    )
    (net (code "35") (name "/DRV_nFLT") (class "Default")
      (node (ref "IC101") (pin "3") (pinfunction "PC14_3") (pintype "passive"))
    )
    (net (code "36") (name "/DRV_nOCTW") (class "Default")
      (node (ref "IC101") (pin "2") (pinfunction "PC13_2") (pintype "passive"))
    )
    (net (code "37") (name "/ENC_A") (class "Default")
      (node (ref "IC101") (pin "59") (pinfunction "PB7_59") (pintype "passive"))
    )
    (net (code "38") (name "/ENC_A_IN") (class "Default")
      (node (ref "J109") (pin "2") (pinfunction "2_2") (pintype "passive"))
    )
    (net (code "39") (name "/ENC_B") (class "Default")
      (node (ref "IC101") (pin "58") (pinfunction "PB6_58") (pintype "passive"))
    )
    (net (code "40") (name "/ENC_B_IN") (class "Default")
      (node (ref "J109") (pin "3") (pinfunction "3_3") (pintype "passive"))
    )
    (net (code "41") (name "/ENC_Z_IN") (class "Default")
      (node (ref "J109") (pin "4") (pinfunction "4_4") (pintype "passive"))
    )
    (net (code "42") (name "/EN_INV") (class "Default")
      (node (ref "IC101") (pin "33") (pinfunction "PB12_33") (pintype "passive"))
    )
    (net (code "43") (name "/F1+") (class "Default")
      (node (ref "J101") (pin "3") (pinfunction "3_3") (pintype "passive"))
    )
    (net (code "44") (name "/F1-") (class "Default")
      (node (ref "J101") (pin "2") (pinfunction "2_2") (pintype "passive"))
    )
    (net (code "45") (name "/F2+") (class "Default")
      (node (ref "J102") (pin "3") (pinfunction "3_3") (pintype "passive"))
    )
    (net (code "46") (name "/F2-") (class "Default")
      (node (ref "J102") (pin "2") (pinfunction "2_2") (pintype "passive"))
    )
    (net (code "47") (name "/HALL_A") (class "Default")
      (node (ref "IC101") (pin "14") (pinfunction "PA0_WKUP_14") (pintype "passive"))
    )
    (net (code "48") (name "/HALL_A_IN") (class "Default")
      (node (ref "J109") (pin "5") (pinfunction "5_5") (pintype "passive"))
    )
    (net (code "49") (name "/HALL_B") (class "Default")
      (node (ref "IC101") (pin "15") (pinfunction "PA1_15") (pintype "passive"))
    )
    (net (code "50") (name "/HALL_B_IN") (class "Default")
      (node (ref "J109") (pin "6") (pinfunction "6_6") (pintype "passive"))
    )
    (net (code "51") (name "/HALL_C") (class "Default")
      (node (ref "IC101") (pin "16") (pinfunction "PA2_16") (pintype "passive"))
    )
    (net (code "52") (name "/HALL_C_IN") (class "Default")
      (node (ref "J109") (pin "7") (pinfunction "7_7") (pintype "passive"))
    )
    (net (code "53") (name "/HX_CK") (class "Default")
      (node (ref "IC101") (pin "28") (pinfunction "PB2_28") (pintype "passive"))
      (node (ref "J104") (pin "6") (pinfunction "6_6") (pintype "passive"))
    )
    (net (code "54") (name "/HX_DT") (class "Default")
      (node (ref "IC101") (pin "29") (pinfunction "PB10_29") (pintype "passive"))
      (node (ref "J104") (pin "8") (pinfunction "8_8") (pintype "passive"))
    )
    (net (code "55") (name "/I2C3_SCL") (class "Default")
      (node (ref "IC101") (pin "41") (pinfunction "PA8_41") (pintype "passive"))
      (node (ref "J104") (pin "14") (pinfunction "14_14") (pintype "passive"))
      (node (ref "R104") (pin "2") (pinfunction "2_2") (pintype "passive"))
    )
    (net (code "56") (name "/I2C3_SDA") (class "Default")
      (node (ref "IC101") (pin "40") (pinfunction "PC9_40") (pintype "passive"))
      (node (ref "J104") (pin "16") (pinfunction "16_16") (pintype "passive"))
      (node (ref "R103") (pin "2") (pinfunction "2_2") (pintype "passive"))
    )
    (net (code "57") (name "/LED1") (class "Default")
      (node (ref "IC101") (pin "51") (pinfunction "PC10_51") (pintype "passive"))
      (node (ref "LED101") (pin "2") (pinfunction "A_2") (pintype "passive"))
    )
    (net (code "58") (name "/LED2") (class "Default")
      (node (ref "IC101") (pin "34") (pinfunction "PB13_34") (pintype "passive"))
      (node (ref "LED102") (pin "2") (pinfunction "A_2") (pintype "passive"))
    )
    (net (code "62") (name "/POS_IN") (class "Default")
      (node (ref "J103") (pin "2") (pinfunction "2_2") (pintype "passive"))
    )
    (net (code "63") (name "/PWM_A_N") (class "Default")
      (node (ref "IC101") (pin "23") (pinfunction "PA7_23") (pintype "passive"))
    )
    (net (code "64") (name "/PWM_A_P") (class "Default")
      (node (ref "IC101") (pin "37") (pinfunction "PC6_37") (pintype "passive"))
    )
    (net (code "65") (name "/PWM_B_N") (class "Default")
      (node (ref "IC101") (pin "35") (pinfunction "PB14_35") (pintype "passive"))
    )
    (net (code "66") (name "/PWM_B_P") (class "Default")
      (node (ref "IC101") (pin "38") (pinfunction "PC7_38") (pintype "passive"))
    )
    (net (code "67") (name "/PWM_C_N") (class "Default")
      (node (ref "IC101") (pin "36") (pinfunction "PB15_36") (pintype "passive"))
    )
    (net (code "68") (name "/PWM_C_P") (class "Default")
      (node (ref "IC101") (pin "39") (pinfunction "PC8_39") (pintype "passive"))
    )
    (net (code "69") (name "/PWM_IN_ENC_Z") (class "Default")
      (node (ref "IC101") (pin "50") (pinfunction "PA15_50") (pintype "passive"))
      (node (ref "J104") (pin "10") (pinfunction "10_10") (pintype "passive"))
    )
    (net (code "73") (name "/RS232_RX") (class "Default")
      (node (ref "IC105") (pin "13") (pinfunction "RIN1_13") (pintype "passive"))
      (node (ref "J107") (pin "2") (pinfunction "2_2") (pintype "passive"))
    )
    (net (code "74") (name "/RS232_TX") (class "Default")
      (node (ref "IC105") (pin "14") (pinfunction "DOUT1_14") (pintype "passive"))
      (node (ref "J107") (pin "1") (pinfunction "1_1") (pintype "passive"))
    )
    (net (code "79") (name "/SPI_MISO") (class "Default")
      (node (ref "IC101") (pin "56") (pinfunction "PB4_56") (pintype "passive"))
      (node (ref "J104") (pin "7") (pinfunction "7_7") (pintype "passive"))
    )
    (net (code "80") (name "/SPI_MOSI") (class "Default")
      (node (ref "IC101") (pin "57") (pinfunction "PB5_57") (pintype "passive"))
      (node (ref "J104") (pin "9") (pinfunction "9_9") (pintype "passive"))
    )
    (net (code "81") (name "/SPI_SCK") (class "Default")
      (node (ref "IC101") (pin "55") (pinfunction "PB3_55") (pintype "passive"))
      (node (ref "J104") (pin "5") (pinfunction "5_5") (pintype "passive"))
    )
    (net (code "82") (name "/SPI_SS1") (class "Default")
      (node (ref "IC101") (pin "54") (pinfunction "PD2_54") (pintype "passive"))
    )
    (net (code "83") (name "/SPI_SS2") (class "Default")
      (node (ref "IC101") (pin "53") (pinfunction "PC12_53") (pintype "passive"))
      (node (ref "J104") (pin "15") (pinfunction "15_15") (pintype "passive"))
    )
    (net (code "84") (name "/SPI_SS3") (class "Default")
      (node (ref "IC101") (pin "52") (pinfunction "PC11_52") (pintype "passive"))
      (node (ref "J104") (pin "13") (pinfunction "13_13") (pintype "passive"))
    )
    (net (code "85") (name "/SWCLK") (class "Default")
      (node (ref "J106") (pin "8") (pinfunction "8_8") (pintype "passive"))
      (node (ref "R109") (pin "2") (pinfunction "2_2") (pintype "passive"))
    )
    (net (code "86") (name "/SWDIO") (class "Default")
      (node (ref "J106") (pin "6") (pinfunction "6_6") (pintype "passive"))
      (node (ref "R108") (pin "2") (pinfunction "2_2") (pintype "passive"))
    )
    (net (code "87") (name "/TH1") (class "Default")
      (node (ref "NT102") (pin "1") (pinfunction "9_1") (pintype "passive"))
    )
    (net (code "88") (name "/UART1_RX") (class "Default")
      (node (ref "D108") (pin "2") (pinfunction "A_2") (pintype "passive"))
      (node (ref "IC101") (pin "43") (pinfunction "PA10_43") (pintype "passive"))
      (node (ref "J106") (pin "3") (pinfunction "3_3") (pintype "passive"))
      (node (ref "LED107") (pin "2") (pinfunction "A_2") (pintype "passive"))
      (node (ref "R105") (pin "2") (pinfunction "2_2") (pintype "passive"))
    )
    (net (code "89") (name "/UART1_TX") (class "Default")
      (node (ref "IC101") (pin "42") (pinfunction "PA9_42") (pintype "passive"))
      (node (ref "IC105") (pin "11") (pinfunction "DIN1_11") (pintype "passive"))
      (node (ref "J106") (pin "5") (pinfunction "5_5") (pintype "passive"))
      (node (ref "LED106") (pin "2") (pinfunction "A_2") (pintype "passive"))
    )
    (net (code "90") (name "/USB_D_N") (class "Default")
      (node (ref "IC101") (pin "44") (pinfunction "PA11_44") (pintype "passive"))
      (node (ref "R125") (pin "1") (pinfunction "1_1") (pintype "passive"))
    )
    (net (code "91") (name "/USB_D_P") (class "Default")
      (node (ref "IC101") (pin "45") (pinfunction "PA12_45") (pintype "passive"))
      (node (ref "R129") (pin "2") (pinfunction "2_2") (pintype "passive"))
    )
    (net (code "92") (name "/nRST") (class "Default")
      (node (ref "C103") (pin "2") (pinfunction "2_2") (pintype "passive"))
      (node (ref "IC101") (pin "7") (pinfunction "NRST_7") (pintype "passive"))
      (node (ref "J106") (pin "2") (pinfunction "2_2") (pintype "passive"))
      (node (ref "R110") (pin "1") (pinfunction "1_1") (pintype "passive"))
      (node (ref "S102") (pin "1") (pinfunction "NO_1_1") (pintype "passive"))
      (node (ref "S102") (pin "2") (pinfunction "NO_2_2") (pintype "passive"))
    )
    (net (code "93") (name "AGND") (class "Default")
      (node (ref "C101") (pin "1") (pinfunction "1_1") (pintype "passive"))
      (node (ref "C102") (pin "1") (pinfunction "1_1") (pintype "passive"))
      (node (ref "C116") (pin "1") (pinfunction "1_1") (pintype "passive"))
      (node (ref "D101") (pin "2") (pinfunction "A_2") (pintype "passive"))
      (node (ref "D102") (pin "2") (pinfunction "A_2") (pintype "passive"))
      (node (ref "D103") (pin "2") (pinfunction "A_2") (pintype "passive"))
      (node (ref "D104") (pin "2") (pinfunction "A_2") (pintype "passive"))
      (node (ref "D105") (pin "2") (pinfunction "A_2") (pintype "passive"))
      (node (ref "IC101") (pin "12") (pinfunction "VSSA_12") (pintype "passive"))
      (node (ref "IC103") (pin "2") (pinfunction "GND_2") (pintype "passive"))
      (node (ref "J105") (pin "6") (pinfunction "6_6") (pintype "passive"))
      (node (ref "NT101") (pin "2") (pinfunction "10_2") (pintype "passive"))
      (node (ref "R106") (pin "1") (pinfunction "1_1") (pintype "passive"))
      (node (ref "R117") (pin "2") (pinfunction "2_2") (pintype "passive"))
      (node (ref "R118") (pin "2") (pinfunction "2_2") (pintype "passive"))
      (node (ref "R119") (pin "2") (pinfunction "2_2") (pintype "passive"))
      (node (ref "R120") (pin "2") (pinfunction "2_2") (pintype "passive"))
      (node (ref "R121") (pin "2") (pinfunction "2_2") (pintype "passive"))
    )
    (net (code "94") (name "AVCC") (class "Default")
      (node (ref "C102") (pin "2") (pinfunction "2_2") (pintype "passive"))
      (node (ref "C116") (pin "2") (pinfunction "2_2") (pintype "passive"))
      (node (ref "IC101") (pin "13") (pinfunction "VDDA_13") (pintype "passive"))
      (node (ref "IC103") (pin "4") (pinfunction "N/C_4") (pintype "passive"))
      (node (ref "IC103") (pin "5") (pinfunction "OUT_5") (pintype "passive"))
      (node (ref "NT102") (pin "2") (pinfunction "10_2") (pintype "passive"))
    )
    (net (code "95") (name "DC_BUS") (class "Default")
      (node (ref "R126") (pin "1") (pinfunction "1_1") (pintype "passive"))
    )
    (net (code "96") (name "GND") (class "Default")
      (node (ref "C103") (pin "1") (pinfunction "1_1") (pintype "passive"))
      (node (ref "C104") (pin "1") (pinfunction "1_1") (pintype "passive"))
      (node (ref "C105") (pin "1") (pinfunction "1_1") (pintype "passive"))
      (node (ref "C106") (pin "1") (pinfunction "1_1") (pintype "passive"))
      (node (ref "C107") (pin "1") (pinfunction "1_1") (pintype "passive"))
      (node (ref "C108") (pin "1") (pinfunction "1_1") (pintype "passive"))
      (node (ref "C109") (pin "1") (pinfunction "1_1") (pintype "passive"))
      (node (ref "C110") (pin "1") (pinfunction "1_1") (pintype "passive"))
      (node (ref "C111") (pin "1") (pinfunction "1_1") (pintype "passive"))
      (node (ref "C112") (pin "1") (pinfunction "1_1") (pintype "passive"))
      (node (ref "C113") (pin "1") (pinfunction "1_1") (pintype "passive"))
      (node (ref "C114") (pin "1") (pinfunction "1_1") (pintype "passive"))
      (node (ref "C115") (pin "1") (pinfunction "1_1") (pintype "passive"))
      (node (ref "C118") (pin "1") (pinfunction "1_1") (pintype "passive"))
      (node (ref "C121") (pin "1") (pinfunction "1_1") (pintype "passive"))
      (node (ref "C122") (pin "1") (pinfunction "1_1") (pintype "passive"))
      (node (ref "C123") (pin "1") (pinfunction "1_1") (pintype "passive"))
      (node (ref "C124") (pin "1") (pinfunction "1_1") (pintype "passive"))
      (node (ref "C125") (pin "1") (pinfunction "1_1") (pintype "passive"))
      (node (ref "D107") (pin "1") (pinfunction "A_1") (pintype "passive"))
      (node (ref "IC101") (pin "18") (pinfunction "VSS_1_18") (pintype "passive"))
      (node (ref "IC101") (pin "63") (pinfunction "VSS_2_63") (pintype "passive"))
      (node (ref "IC102") (pin "1") (pinfunction "GND/ADJ_1") (pintype "passive"))
      (node (ref "IC104") (pin "2") (pinfunction "GND_2") (pintype "passive"))
      (node (ref "IC105") (pin "10") (pinfunction "DIN2_10") (pintype "passive"))
      (node (ref "IC105") (pin "15") (pinfunction "GND_15") (pintype "passive"))
      (node (ref "IC105") (pin "8") (pinfunction "RIN2_8") (pintype "passive"))
      (node (ref "J101") (pin "4") (pinfunction "4_4") (pintype "passive"))
      (node (ref "J102") (pin "4") (pinfunction "4_4") (pintype "passive"))
      (node (ref "J103") (pin "3") (pinfunction "3_3") (pintype "passive"))
      (node (ref "J104") (pin "11") (pinfunction "11_11") (pintype "passive"))
      (node (ref "J104") (pin "12") (pinfunction "12_12") (pintype "passive"))
      (node (ref "J106") (pin "10") (pinfunction "10_10") (pintype "passive"))
      (node (ref "J106") (pin "9") (pinfunction "9_9") (pintype "passive"))
      (node (ref "J107") (pin "3") (pinfunction "3_3") (pintype "passive"))
      (node (ref "J108") (pin "3") (pinfunction "3_3") (pintype "passive"))
      (node (ref "J109") (pin "8") (pinfunction "8_8") (pintype "passive"))
      (node (ref "J110") (pin "5") (pinfunction "5_5") (pintype "passive"))
      (node (ref "J110") (pin "MH1") (pinfunction "MH1_MH1") (pintype "passive"))
      (node (ref "J110") (pin "MH2") (pinfunction "MH2_MH2") (pintype "passive"))
      (node (ref "LED103") (pin "1") (pinfunction "K_1") (pintype "passive"))
      (node (ref "NT101") (pin "1") (pinfunction "9_1") (pintype "passive"))
      (node (ref "R116") (pin "1") (pinfunction "1_1") (pintype "passive"))
      (node (ref "R130") (pin "2") (pinfunction "2_2") (pintype "passive"))
      (node (ref "S102") (pin "3") (pinfunction "COM_1_3") (pintype "passive"))
      (node (ref "S102") (pin "4") (pinfunction "COM_2_4") (pintype "passive"))
      (node (ref "Y101") (pin "2") (pinfunction "GND_&_LID_1_2") (pintype "passive"))
      (node (ref "Y101") (pin "4") (pinfunction "GND_&_LID_2_4") (pintype "passive"))
    )
    (net (code "97") (name "Net-(D107-K-Pad2)") (class "Default")
      (node (ref "D107") (pin "2") (pinfunction "K_2") (pintype "passive"))
      (node (ref "J110") (pin "2") (pinfunction "2_2") (pintype "passive"))
      (node (ref "R125") (pin "2") (pinfunction "2_2") (pintype "passive"))
    )
    (net (code "98") (name "Net-(D107-K-Pad3)") (class "Default")
      (node (ref "D107") (pin "3") (pinfunction "K_3") (pintype "passive"))
      (node (ref "J110") (pin "3") (pinfunction "3_3") (pintype "passive"))
      (node (ref "R129") (pin "1") (pinfunction "1_1") (pintype "passive"))
    )
    (net (code "99") (name "Net-(D108-K)") (class "Default")
      (node (ref "D108") (pin "1") (pinfunction "K_1") (pintype "passive"))
      (node (ref "IC105") (pin "12") (pinfunction "ROUT1_12") (pintype "passive"))
    )
    (net (code "100") (name "Net-(D109-A)") (class "Default")
      (node (ref "D107") (pin "4") (pinfunction "K_4") (pintype "passive"))
      (node (ref "D109") (pin "2") (pinfunction "A_2") (pintype "passive"))
      (node (ref "J110") (pin "1") (pinfunction "1_1") (pintype "passive"))
    )
    (net (code "101") (name "Net-(IC101-PA13)") (class "Default")
      (node (ref "IC101") (pin "46") (pinfunction "PA13_46") (pintype "passive"))
      (node (ref "R108") (pin "1") (pinfunction "1_1") (pintype "passive"))
    )
    (net (code "102") (name "Net-(IC101-PA14)") (class "Default")
      (node (ref "IC101") (pin "49") (pinfunction "PA14_49") (pintype "passive"))
      (node (ref "R109") (pin "1") (pinfunction "1_1") (pintype "passive"))
    )
    (net (code "103") (name "Net-(IC101-PH0)") (class "Default")
      (node (ref "C110") (pin "2") (pinfunction "2_2") (pintype "passive"))
      (node (ref "IC101") (pin "5") (pinfunction "PH0_5") (pintype "passive"))
      (node (ref "Y101") (pin "1") (pinfunction "CRYSTAL__1_1") (pintype "passive"))
    )
    (net (code "104") (name "Net-(IC101-PH1)") (class "Default")
      (node (ref "C111") (pin "2") (pinfunction "2_2") (pintype "passive"))
      (node (ref "IC101") (pin "6") (pinfunction "PH1_6") (pintype "passive"))
      (node (ref "Y101") (pin "3") (pinfunction "CRYSTAL__2_3") (pintype "passive"))
    )
    (net (code "105") (name "Net-(IC101-VCAP_1)") (class "Default")
      (node (ref "C108") (pin "2") (pinfunction "2_2") (pintype "passive"))
      (node (ref "IC101") (pin "31") (pinfunction "VCAP_1_31") (pintype "passive"))
    )
    (net (code "106") (name "Net-(IC101-VCAP_2)") (class "Default")
      (node (ref "C109") (pin "2") (pinfunction "2_2") (pintype "passive"))
      (node (ref "IC101") (pin "47") (pinfunction "VCAP_2_47") (pintype "passive"))
    )
    (net (code "107") (name "Net-(IC103-EN)") (class "Default")
      (node (ref "C115") (pin "2") (pinfunction "2_2") (pintype "passive"))
      (node (ref "FB101") (pin "2") (pinfunction "2_2") (pintype "passive"))
      (node (ref "IC103") (pin "1") (pinfunction "IN_1") (pintype "passive"))
      (node (ref "IC103") (pin "3") (pinfunction "EN_3") (pintype "passive"))
    )
    (net (code "108") (name "Net-(IC105-C1+)") (class "Default")
      (node (ref "C117") (pin "1") (pinfunction "1_1") (pintype "passive"))
      (node (ref "IC105") (pin "1") (pinfunction "C1+_1") (pintype "passive"))
    )
    (net (code "109") (name "Net-(IC105-C1-)") (class "Default")
      (node (ref "C117") (pin "2") (pinfunction "2_2") (pintype "passive"))
      (node (ref "IC105") (pin "3") (pinfunction "C1-_3") (pintype "passive"))
    )
    (net (code "110") (name "Net-(IC105-C2+)") (class "Default")
      (node (ref "C120") (pin "1") (pinfunction "1_1") (pintype "passive"))
      (node (ref "IC105") (pin "4") (pinfunction "C2+_4") (pintype "passive"))
    )
    (net (code "111") (name "Net-(IC105-C2-)") (class "Default")
      (node (ref "C120") (pin "2") (pinfunction "2_2") (pintype "passive"))
      (node (ref "IC105") (pin "5") (pinfunction "C2-_5") (pintype "passive"))
    )
    (net (code "112") (name "Net-(IC105-V+)") (class "Default")
      (node (ref "C119") (pin "2") (pinfunction "2_2") (pintype "passive"))
      (node (ref "IC105") (pin "2") (pinfunction "V+_2") (pintype "passive"))
    )
    (net (code "113") (name "Net-(IC105-V-)") (class "Default")
      (node (ref "C121") (pin "2") (pinfunction "2_2") (pintype "passive"))
      (node (ref "IC105") (pin "6") (pinfunction "V-_6") (pintype "passive"))
    )
    (net (code "114") (name "Net-(J105-Pad1)") (class "Default")
      (node (ref "J105") (pin "1") (pinfunction "1_1") (pintype "passive"))
      (node (ref "R111") (pin "2") (pinfunction "2_2") (pintype "passive"))
    )
    (net (code "115") (name "Net-(J105-Pad2)") (class "Default")
      (node (ref "J105") (pin "2") (pinfunction "2_2") (pintype "passive"))
      (node (ref "R112") (pin "2") (pinfunction "2_2") (pintype "passive"))
    )
    (net (code "116") (name "Net-(J105-Pad3)") (class "Default")
      (node (ref "J105") (pin "3") (pinfunction "3_3") (pintype "passive"))
      (node (ref "R113") (pin "2") (pinfunction "2_2") (pintype "passive"))
    )
    (net (code "117") (name "Net-(J105-Pad4)") (class "Default")
      (node (ref "J105") (pin "4") (pinfunction "4_4") (pintype "passive"))
      (node (ref "R114") (pin "2") (pinfunction "2_2") (pintype "passive"))
    )
    (net (code "118") (name "Net-(J105-Pad5)") (class "Default")
      (node (ref "J105") (pin "5") (pinfunction "5_5") (pintype "passive"))
      (node (ref "R115") (pin "2") (pinfunction "2_2") (pintype "passive"))
    )
    (net (code "119") (name "Net-(JP101-Pad2)") (class "Default")
      (node (ref "JP101") (pin "2") (pintype "passive"))
      (node (ref "R124") (pin "1") (pinfunction "1_1") (pintype "passive"))
    )
    (net (code "120") (name "Net-(LED101-K)") (class "Default")
      (node (ref "LED101") (pin "1") (pinfunction "K_1") (pintype "passive"))
      (node (ref "R102") (pin "2") (pinfunction "2_2") (pintype "passive"))
    )
    (net (code "121") (name "Net-(LED102-K)") (class "Default")
      (node (ref "LED102") (pin "1") (pinfunction "K_1") (pintype "passive"))
      (node (ref "R101") (pin "2") (pinfunction "2_2") (pintype "passive"))
    )
    (net (code "122") (name "Net-(LED103-A)") (class "Default")
      (node (ref "LED103") (pin "2") (pinfunction "A_2") (pintype "passive"))
      (node (ref "R107") (pin "1") (pinfunction "1_1") (pintype "passive"))
    )
    (net (code "123") (name "Net-(LED104-K)") (class "Default")
      (node (ref "LED104") (pin "1") (pinfunction "K_1") (pintype "passive"))
      (node (ref "R123") (pin "1") (pinfunction "1_1") (pintype "passive"))
    )
    (net (code "124") (name "Net-(LED105-K)") (class "Default")
      (node (ref "LED105") (pin "1") (pinfunction "K_1") (pintype "passive"))
      (node (ref "R122") (pin "1") (pinfunction "1_1") (pintype "passive"))
    )
    (net (code "125") (name "Net-(LED106-K)") (class "Default")
      (node (ref "LED106") (pin "1") (pinfunction "K_1") (pintype "passive"))
      (node (ref "R128") (pin "1") (pinfunction "1_1") (pintype "passive"))
    )
    (net (code "126") (name "Net-(LED107-K)") (class "Default")
      (node (ref "LED107") (pin "1") (pinfunction "K_1") (pintype "passive"))
      (node (ref "R127") (pin "1") (pinfunction "1_1") (pintype "passive"))
    )
    (net (code "127") (name "VDD") (class "Default")
      (node (ref "C104") (pin "2") (pinfunction "2_2") (pintype "passive"))
      (node (ref "C105") (pin "2") (pinfunction "2_2") (pintype "passive"))
      (node (ref "C106") (pin "2") (pinfunction "2_2") (pintype "passive"))
      (node (ref "C107") (pin "2") (pinfunction "2_2") (pintype "passive"))
      (node (ref "C112") (pin "2") (pinfunction "2_2") (pintype "passive"))
      (node (ref "C113") (pin "2") (pinfunction "2_2") (pintype "passive"))
      (node (ref "C114") (pin "2") (pinfunction "2_2") (pintype "passive"))
      (node (ref "C118") (pin "2") (pinfunction "2_2") (pintype "passive"))
      (node (ref "C119") (pin "1") (pinfunction "1_1") (pintype "passive"))
      (node (ref "D106") (pin "1") (pinfunction "K_1") (pintype "passive"))
      (node (ref "IC101") (pin "1") (pinfunction "VBAT_1") (pintype "passive"))
      (node (ref "IC101") (pin "19") (pinfunction "VDD_1_19") (pintype "passive"))
      (node (ref "IC101") (pin "32") (pinfunction "VDD_2_32") (pintype "passive"))
      (node (ref "IC101") (pin "48") (pinfunction "VDD_3_48") (pintype "passive"))
      (node (ref "IC101") (pin "64") (pinfunction "VDD_4_64") (pintype "passive"))
      (node (ref "IC102") (pin "2") (pinfunction "VOUT_2") (pintype "passive"))
      (node (ref "IC102") (pin "4") (pinfunction "NC_4") (pintype "passive"))
      (node (ref "IC104") (pin "3") (pinfunction "VCC_3") (pintype "passive"))
      (node (ref "IC105") (pin "16") (pinfunction "VCC_16") (pintype "passive"))
      (node (ref "J104") (pin "3") (pinfunction "3_3") (pintype "passive"))
      (node (ref "J104") (pin "4") (pinfunction "4_4") (pintype "passive"))
      (node (ref "J106") (pin "1") (pinfunction "1_1") (pintype "passive"))
      (node (ref "R101") (pin "1") (pinfunction "1_1") (pintype "passive"))
      (node (ref "R102") (pin "1") (pinfunction "1_1") (pintype "passive"))
      (node (ref "R103") (pin "1") (pinfunction "1_1") (pintype "passive"))
      (node (ref "R104") (pin "1") (pinfunction "1_1") (pintype "passive"))
      (node (ref "R105") (pin "1") (pinfunction "1_1") (pintype "passive"))
      (node (ref "R107") (pin "2") (pinfunction "2_2") (pintype "passive"))
      (node (ref "R110") (pin "2") (pinfunction "2_2") (pintype "passive"))
      (node (ref "R122") (pin "2") (pinfunction "2_2") (pintype "passive"))
      (node (ref "R123") (pin "2") (pinfunction "2_2") (pintype "passive"))
      (node (ref "R127") (pin "2") (pinfunction "2_2") (pintype "passive"))
      (node (ref "R128") (pin "2") (pinfunction "2_2") (pintype "passive"))
      (node (ref "S101") (pin "1") (pinfunction "NO_1_1") (pintype "passive"))
      (node (ref "S101") (pin "2") (pinfunction "NO_2_2") (pintype "passive"))
    )
    (net (code "128") (name "unconnected-(IC104-NC_1-Pad5)") (class "Default")
      (node (ref "IC104") (pin "5") (pinfunction "NC_1_5") (pintype "passive"))
    )
    (net (code "129") (name "unconnected-(IC104-NC_2-Pad8)") (class "Default")
      (node (ref "IC104") (pin "8") (pinfunction "NC_2_8") (pintype "passive"))
    )
    (net (code "130") (name "unconnected-(IC105-DOUT2-Pad7)") (class "Default")
      (node (ref "IC105") (pin "7") (pinfunction "DOUT2_7") (pintype "passive"))
    )
    (net (code "131") (name "unconnected-(IC105-ROUT2-Pad9)") (class "Default")
      (node (ref "IC105") (pin "9") (pinfunction "ROUT2_9") (pintype "passive"))
    )
    (net (code "132") (name "unconnected-(J110-Pad4)") (class "Default")
      (node (ref "J110") (pin "4") (pinfunction "4_4") (pintype "passive"))
    )
  )
)
